# relay_control.net
KiCad netlist of a schematic drawn in EAGLE
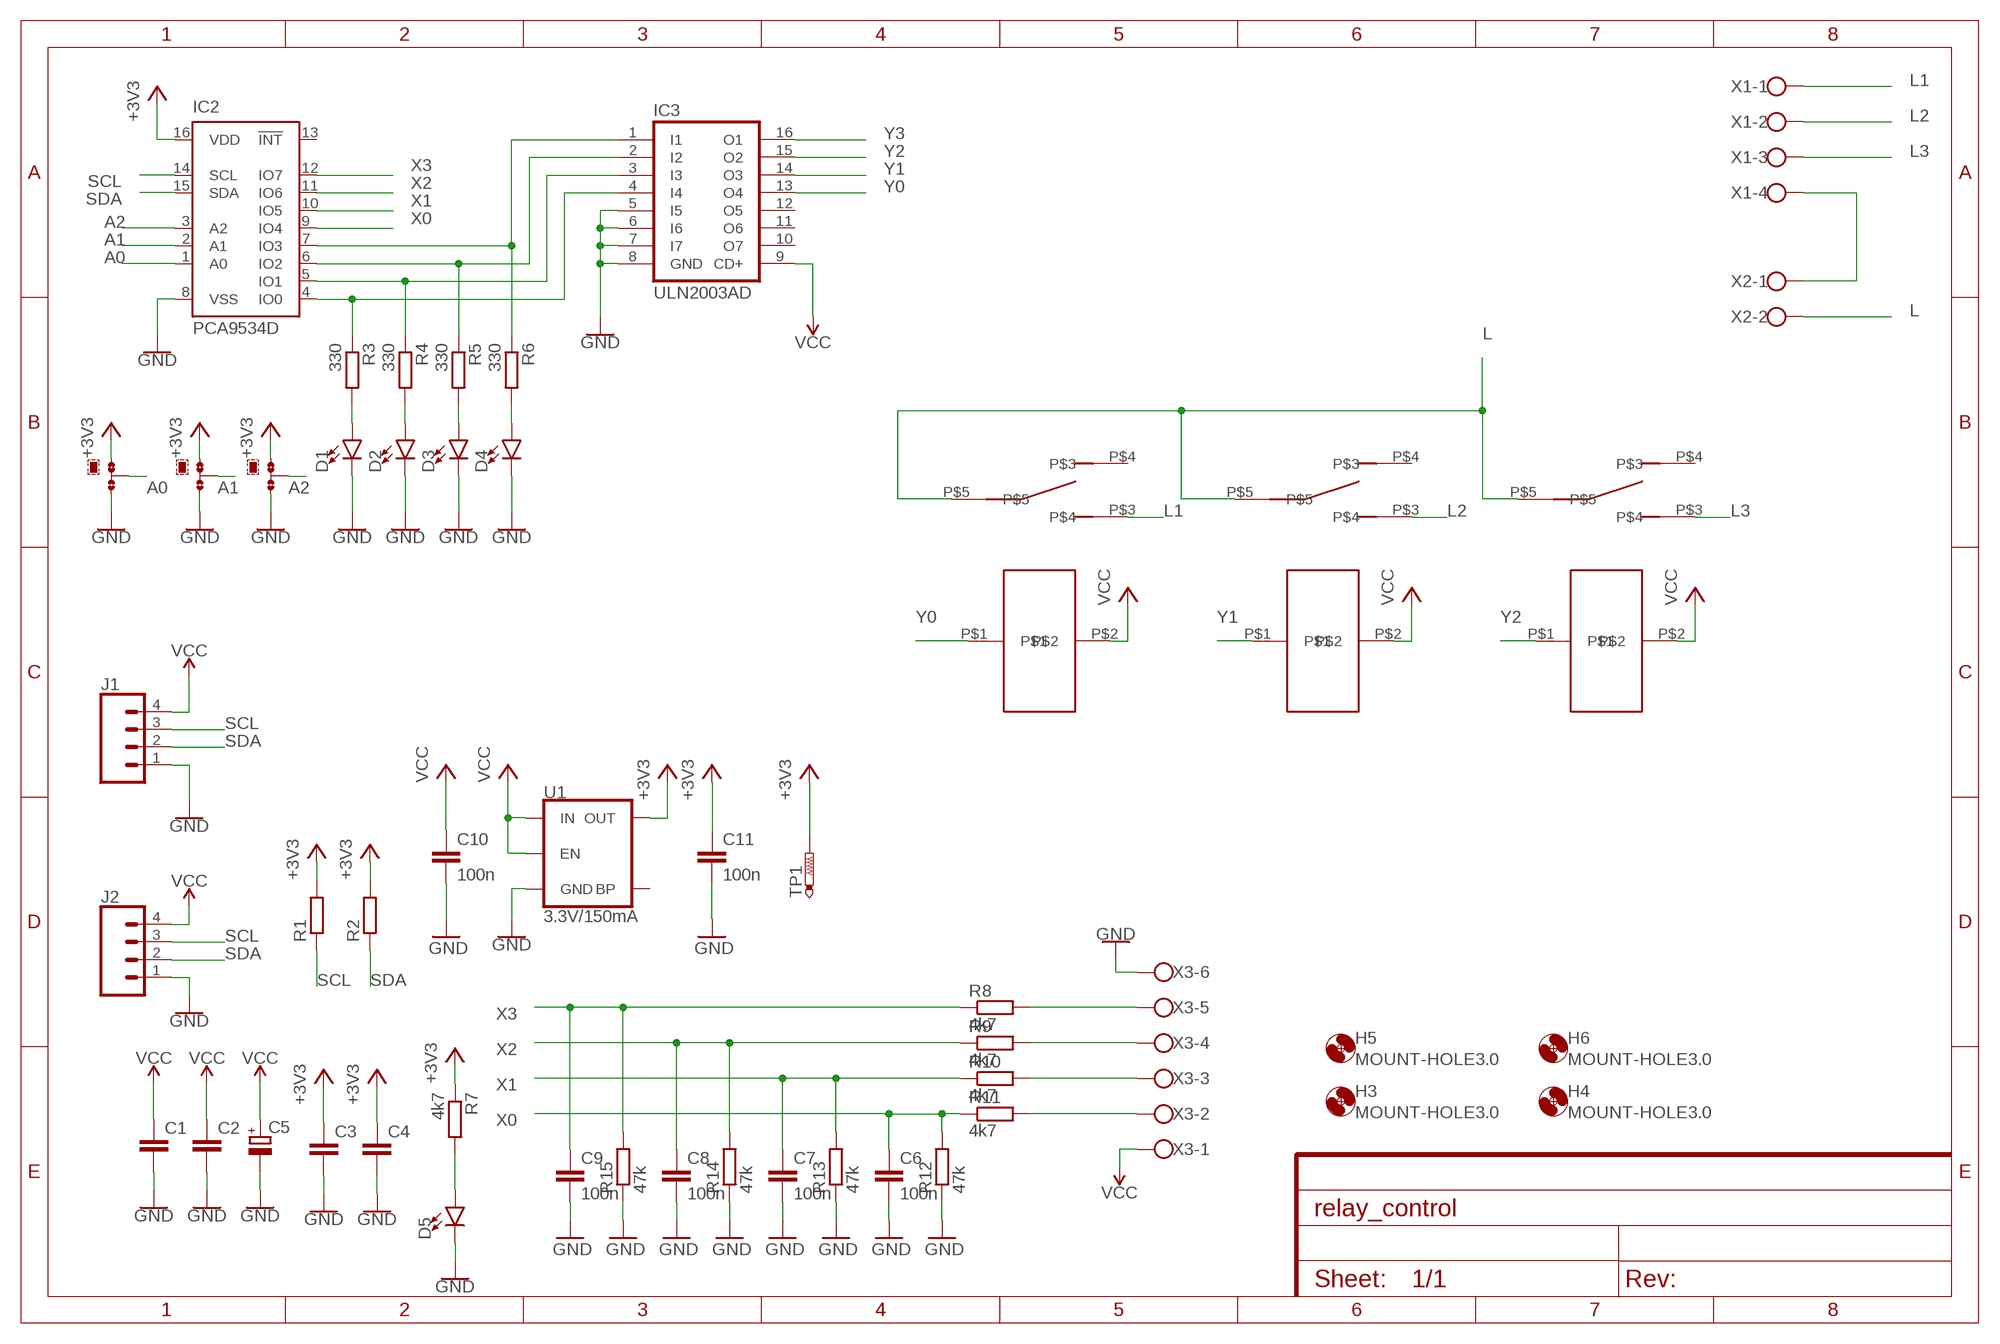
[diagram p0: schematic, sheet 1]

(export (version "E")
  (design (tool "Eeschema 10.0.6"))
  (components
    (comp (ref "C1")
      (value "C-EUC0805")
      (footprint "eagle-import:C0805")
      (libsource (lib "eagle-import") (part "C-EUC0805"))
    )
    (comp (ref "C2")
      (value "C-EUC0805")
      (footprint "eagle-import:C0805")
      (libsource (lib "eagle-import") (part "C-EUC0805"))
    )
    (comp (ref "C3")
      (value "C-EUC0805")
      (footprint "eagle-import:C0805")
      (libsource (lib "eagle-import") (part "C-EUC0805"))
    )
    (comp (ref "C4")
      (value "C-EUC0805")
      (footprint "eagle-import:C0805")
      (libsource (lib "eagle-import") (part "C-EUC0805"))
    )
    (comp (ref "C5")
      (value "CPOL-EU150CLZ-1014")
      (footprint "eagle-import:150CLZ-1014")
      (libsource (lib "eagle-import") (part "CPOL-EU150CLZ-1014"))
    )
    (comp (ref "C6")
      (value "100n")
      (footprint "eagle-import:C0805")
      (libsource (lib "eagle-import") (part "C-EUC0805"))
    )
    (comp (ref "C7")
      (value "100n")
      (footprint "eagle-import:C0805")
      (libsource (lib "eagle-import") (part "C-EUC0805"))
    )
    (comp (ref "C8")
      (value "100n")
      (footprint "eagle-import:C0805")
      (libsource (lib "eagle-import") (part "C-EUC0805"))
    )
    (comp (ref "C9")
      (value "100n")
      (footprint "eagle-import:C0805")
      (libsource (lib "eagle-import") (part "C-EUC0805"))
    )
    (comp (ref "C10")
      (value "100n")
      (footprint "eagle-import:C0805")
      (libsource (lib "eagle-import") (part "C-EUC0805"))
    )
    (comp (ref "C11")
      (value "100n")
      (footprint "eagle-import:C0805")
      (libsource (lib "eagle-import") (part "C-EUC0805"))
    )
    (comp (ref "D1")
      (value "LED1206")
      (footprint "eagle-import:LED-1206")
      (libsource (lib "eagle-import") (part "LED1206"))
    )
    (comp (ref "D2")
      (value "LED1206")
      (footprint "eagle-import:LED-1206")
      (libsource (lib "eagle-import") (part "LED1206"))
    )
    (comp (ref "D3")
      (value "LED1206")
      (footprint "eagle-import:LED-1206")
      (libsource (lib "eagle-import") (part "LED1206"))
    )
    (comp (ref "D4")
      (value "LED1206")
      (footprint "eagle-import:LED-1206")
      (libsource (lib "eagle-import") (part "LED1206"))
    )
    (comp (ref "D5")
      (value "LED1206")
      (footprint "eagle-import:LED-1206")
      (libsource (lib "eagle-import") (part "LED1206"))
    )
    (comp (ref "H3")
      (value "MOUNT-HOLE3.0")
      (footprint "eagle-import:3,0")
      (libsource (lib "eagle-import") (part "MOUNT-HOLE3.0"))
    )
    (comp (ref "H4")
      (value "MOUNT-HOLE3.0")
      (footprint "eagle-import:3,0")
      (libsource (lib "eagle-import") (part "MOUNT-HOLE3.0"))
    )
    (comp (ref "H5")
      (value "MOUNT-HOLE3.0")
      (footprint "eagle-import:3,0")
      (libsource (lib "eagle-import") (part "MOUNT-HOLE3.0"))
    )
    (comp (ref "H6")
      (value "MOUNT-HOLE3.0")
      (footprint "eagle-import:3,0")
      (libsource (lib "eagle-import") (part "MOUNT-HOLE3.0"))
    )
    (comp (ref "IC2")
      (value "PCA9534D")
      (footprint "eagle-import:SO16W")
      (fields (field (name "MPN") "PCA9534DB"))
      (libsource (lib "eagle-import") (part "PCA9534D"))
    )
    (comp (ref "IC3")
      (value "ULN2003AD")
      (footprint "eagle-import:SO16")
      (libsource (lib "eagle-import") (part "ULN2003AD"))
    )
    (comp (ref "J1")
      (value "CONN_04POLAR")
      (footprint "eagle-import:MOLEX-1X4")
      (libsource (lib "eagle-import") (part "CONN_04POLAR"))
    )
    (comp (ref "J2")
      (value "CONN_04POLAR")
      (footprint "eagle-import:MOLEX-1X4")
      (libsource (lib "eagle-import") (part "CONN_04POLAR"))
    )
    (comp (ref "JMP1")
      (value "0R-JUMPA")
      (footprint "eagle-import:A0R-JMP")
      (libsource (lib "eagle-import") (part "0R-JUMPA"))
    )
    (comp (ref "JMP2")
      (value "0R-JUMPA")
      (footprint "eagle-import:A0R-JMP")
      (libsource (lib "eagle-import") (part "0R-JUMPA"))
    )
    (comp (ref "JMP3")
      (value "0R-JUMPA")
      (footprint "eagle-import:A0R-JMP")
      (libsource (lib "eagle-import") (part "0R-JUMPA"))
    )
    (comp (ref "R1")
      (value "R-EU_M0805")
      (footprint "eagle-import:M0805")
      (libsource (lib "eagle-import") (part "R-EU_M0805"))
    )
    (comp (ref "R2")
      (value "R-EU_M0805")
      (footprint "eagle-import:M0805")
      (libsource (lib "eagle-import") (part "R-EU_M0805"))
    )
    (comp (ref "R3")
      (value "330")
      (footprint "eagle-import:M0805")
      (libsource (lib "eagle-import") (part "R-EU_M0805"))
    )
    (comp (ref "R4")
      (value "330")
      (footprint "eagle-import:M0805")
      (libsource (lib "eagle-import") (part "R-EU_M0805"))
    )
    (comp (ref "R5")
      (value "330")
      (footprint "eagle-import:M0805")
      (libsource (lib "eagle-import") (part "R-EU_M0805"))
    )
    (comp (ref "R6")
      (value "330")
      (footprint "eagle-import:M0805")
      (libsource (lib "eagle-import") (part "R-EU_M0805"))
    )
    (comp (ref "R7")
      (value "4k7")
      (footprint "eagle-import:M0805")
      (libsource (lib "eagle-import") (part "R-EU_M0805"))
    )
    (comp (ref "R8")
      (value "4k7")
      (footprint "eagle-import:M0805")
      (libsource (lib "eagle-import") (part "R-EU_M0805"))
    )
    (comp (ref "R9")
      (value "4k7")
      (footprint "eagle-import:M0805")
      (libsource (lib "eagle-import") (part "R-EU_M0805"))
    )
    (comp (ref "R10")
      (value "4k7")
      (footprint "eagle-import:M0805")
      (libsource (lib "eagle-import") (part "R-EU_M0805"))
    )
    (comp (ref "R11")
      (value "4k7")
      (footprint "eagle-import:M0805")
      (libsource (lib "eagle-import") (part "R-EU_M0805"))
    )
    (comp (ref "R12")
      (value "47k")
      (footprint "eagle-import:M0805")
      (libsource (lib "eagle-import") (part "R-EU_M0805"))
    )
    (comp (ref "R13")
      (value "47k")
      (footprint "eagle-import:M0805")
      (libsource (lib "eagle-import") (part "R-EU_M0805"))
    )
    (comp (ref "R14")
      (value "47k")
      (footprint "eagle-import:M0805")
      (libsource (lib "eagle-import") (part "R-EU_M0805"))
    )
    (comp (ref "R15")
      (value "47k")
      (footprint "eagle-import:M0805")
      (libsource (lib "eagle-import") (part "R-EU_M0805"))
    )
    (comp (ref "TP1")
      (value "PTR1B2,54")
      (footprint "eagle-import:B2,54")
      (libsource (lib "eagle-import") (part "PTR1B2,54"))
    )
    (comp (ref "U$1")
      (value "T9G_RELAY")
      (footprint "eagle-import:T9G_RELAY")
      (libsource (lib "eagle-import") (part "T9G_RELAY"))
    )
    (comp (ref "U$2")
      (value "T9G_RELAY")
      (footprint "eagle-import:T9G_RELAY")
      (libsource (lib "eagle-import") (part "T9G_RELAY"))
    )
    (comp (ref "U$3")
      (value "T9G_RELAY")
      (footprint "eagle-import:T9G_RELAY")
      (libsource (lib "eagle-import") (part "T9G_RELAY"))
    )
    (comp (ref "U1")
      (value "3.3V/150mA")
      (footprint "eagle-import:SOT23-5")
      (libsource (lib "eagle-import") (part "V_REG_MIC52053.3V"))
    )
    (comp (ref "X1")
      (value "W239-104")
      (footprint "eagle-import:W239-104")
      (libsource (lib "eagle-import") (part "W239-104"))
    )
    (comp (ref "X2")
      (value "W239-302")
      (footprint "eagle-import:W239-302")
      (libsource (lib "eagle-import") (part "W239-302"))
    )
    (comp (ref "X3")
      (value "W237-6")
      (footprint "eagle-import:W237-6")
      (libsource (lib "eagle-import") (part "W237-6"))
    )
  )
  (nets
    (net (code "1") (name "+3V3") (class "Default")
      (node (ref "C11") (pin "1") (pinfunction "1_1") (pintype "passive"))
      (node (ref "C3") (pin "1") (pinfunction "1_1") (pintype "passive"))
      (node (ref "C4") (pin "1") (pinfunction "1_1") (pintype "passive"))
      (node (ref "IC2") (pin "16") (pinfunction "VDD_16") (pintype "power_in"))
      (node (ref "JMP1") (pin "1") (pinfunction "1_1") (pintype "passive"))
      (node (ref "JMP2") (pin "1") (pinfunction "1_1") (pintype "passive"))
      (node (ref "JMP3") (pin "1") (pinfunction "1_1") (pintype "passive"))
      (node (ref "R1") (pin "2") (pinfunction "2_2") (pintype "passive"))
      (node (ref "R2") (pin "2") (pinfunction "2_2") (pintype "passive"))
      (node (ref "R7") (pin "1") (pinfunction "1_1") (pintype "passive"))
      (node (ref "TP1") (pin "TP") (pinfunction "TP_TP") (pintype "input"))
      (node (ref "U1") (pin "5") (pinfunction "OUT_5") (pintype "passive"))
    )
    (net (code "2") (name "/A0") (class "Default")
      (node (ref "IC2") (pin "1") (pinfunction "A0_1") (pintype "input"))
      (node (ref "JMP1") (pin "2") (pinfunction "2_2") (pintype "passive"))
    )
    (net (code "3") (name "/A1") (class "Default")
      (node (ref "IC2") (pin "2") (pinfunction "A1_2") (pintype "input"))
      (node (ref "JMP2") (pin "2") (pinfunction "2_2") (pintype "passive"))
    )
    (net (code "4") (name "/A2") (class "Default")
      (node (ref "IC2") (pin "3") (pinfunction "A2_3") (pintype "input"))
      (node (ref "JMP3") (pin "2") (pinfunction "2_2") (pintype "passive"))
    )
    (net (code "5") (name "/L") (class "Default")
      (node (ref "U$1") (pin "P$5") (pinfunction "P$5_P$5") (pintype "bidirectional"))
      (node (ref "U$2") (pin "P$5") (pinfunction "P$5_P$5") (pintype "bidirectional"))
      (node (ref "U$3") (pin "P$5") (pinfunction "P$5_P$5") (pintype "bidirectional"))
      (node (ref "X2") (pin "2") (pinfunction "KL_2") (pintype "passive"))
    )
    (net (code "6") (name "/L1") (class "Default")
      (node (ref "U$1") (pin "P$3") (pinfunction "P$4_P$3") (pintype "bidirectional"))
      (node (ref "X1") (pin "1") (pinfunction "KL_1") (pintype "passive"))
    )
    (net (code "7") (name "/L2") (class "Default")
      (node (ref "U$2") (pin "P$3") (pinfunction "P$4_P$3") (pintype "bidirectional"))
      (node (ref "X1") (pin "2") (pinfunction "KL_2") (pintype "passive"))
    )
    (net (code "8") (name "/L3") (class "Default")
      (node (ref "U$3") (pin "P$3") (pinfunction "P$4_P$3") (pintype "bidirectional"))
      (node (ref "X1") (pin "3") (pinfunction "KL_3") (pintype "passive"))
    )
    (net (code "9") (name "/SCL") (class "Default")
      (node (ref "IC2") (pin "14") (pinfunction "SCL_14") (pintype "input"))
      (node (ref "J1") (pin "3") (pinfunction "3_3") (pintype "passive"))
      (node (ref "J2") (pin "3") (pinfunction "3_3") (pintype "passive"))
      (node (ref "R1") (pin "1") (pinfunction "1_1") (pintype "passive"))
    )
    (net (code "10") (name "/SDA") (class "Default")
      (node (ref "IC2") (pin "15") (pinfunction "SDA_15") (pintype "bidirectional"))
      (node (ref "J1") (pin "2") (pinfunction "2_2") (pintype "passive"))
      (node (ref "J2") (pin "2") (pinfunction "2_2") (pintype "passive"))
      (node (ref "R2") (pin "1") (pinfunction "1_1") (pintype "passive"))
    )
    (net (code "11") (name "/X0") (class "Default")
      (node (ref "C6") (pin "1") (pinfunction "1_1") (pintype "passive"))
      (node (ref "IC2") (pin "9") (pinfunction "IO4_9") (pintype "bidirectional"))
      (node (ref "R11") (pin "1") (pinfunction "1_1") (pintype "passive"))
      (node (ref "R12") (pin "2") (pinfunction "2_2") (pintype "passive"))
    )
    (net (code "12") (name "/X1") (class "Default")
      (node (ref "C7") (pin "1") (pinfunction "1_1") (pintype "passive"))
      (node (ref "IC2") (pin "10") (pinfunction "IO5_10") (pintype "bidirectional"))
      (node (ref "R10") (pin "1") (pinfunction "1_1") (pintype "passive"))
      (node (ref "R13") (pin "2") (pinfunction "2_2") (pintype "passive"))
    )
    (net (code "13") (name "/X2") (class "Default")
      (node (ref "C8") (pin "1") (pinfunction "1_1") (pintype "passive"))
      (node (ref "IC2") (pin "11") (pinfunction "IO6_11") (pintype "bidirectional"))
      (node (ref "R14") (pin "2") (pinfunction "2_2") (pintype "passive"))
      (node (ref "R9") (pin "1") (pinfunction "1_1") (pintype "passive"))
    )
    (net (code "14") (name "/X3") (class "Default")
      (node (ref "C9") (pin "1") (pinfunction "1_1") (pintype "passive"))
      (node (ref "IC2") (pin "12") (pinfunction "IO7_12") (pintype "bidirectional"))
      (node (ref "R15") (pin "2") (pinfunction "2_2") (pintype "passive"))
      (node (ref "R8") (pin "1") (pinfunction "1_1") (pintype "passive"))
    )
    (net (code "15") (name "/Y0") (class "Default")
      (node (ref "IC3") (pin "13") (pinfunction "O4_13") (pintype "open_collector"))
      (node (ref "U$1") (pin "P$1") (pinfunction "P$1_P$1") (pintype "bidirectional"))
    )
    (net (code "16") (name "/Y1") (class "Default")
      (node (ref "IC3") (pin "14") (pinfunction "O3_14") (pintype "open_collector"))
      (node (ref "U$2") (pin "P$1") (pinfunction "P$1_P$1") (pintype "bidirectional"))
    )
    (net (code "17") (name "/Y2") (class "Default")
      (node (ref "IC3") (pin "15") (pinfunction "O2_15") (pintype "open_collector"))
      (node (ref "U$3") (pin "P$1") (pinfunction "P$1_P$1") (pintype "bidirectional"))
    )
    (net (code "18") (name "/Y3") (class "Default")
      (node (ref "IC3") (pin "16") (pinfunction "O1_16") (pintype "open_collector"))
    )
    (net (code "19") (name "GND") (class "Default")
      (node (ref "C1") (pin "2") (pinfunction "2_2") (pintype "passive"))
      (node (ref "C10") (pin "2") (pinfunction "2_2") (pintype "passive"))
      (node (ref "C11") (pin "2") (pinfunction "2_2") (pintype "passive"))
      (node (ref "C2") (pin "2") (pinfunction "2_2") (pintype "passive"))
      (node (ref "C3") (pin "2") (pinfunction "2_2") (pintype "passive"))
      (node (ref "C4") (pin "2") (pinfunction "2_2") (pintype "passive"))
      (node (ref "C5") (pin "-") (pinfunction "-_-") (pintype "passive"))
      (node (ref "C6") (pin "2") (pinfunction "2_2") (pintype "passive"))
      (node (ref "C7") (pin "2") (pinfunction "2_2") (pintype "passive"))
      (node (ref "C8") (pin "2") (pinfunction "2_2") (pintype "passive"))
      (node (ref "C9") (pin "2") (pinfunction "2_2") (pintype "passive"))
      (node (ref "D1") (pin "C") (pinfunction "C_C") (pintype "passive"))
      (node (ref "D2") (pin "C") (pinfunction "C_C") (pintype "passive"))
      (node (ref "D3") (pin "C") (pinfunction "C_C") (pintype "passive"))
      (node (ref "D4") (pin "C") (pinfunction "C_C") (pintype "passive"))
      (node (ref "D5") (pin "C") (pinfunction "C_C") (pintype "passive"))
      (node (ref "IC2") (pin "8") (pinfunction "VSS_8") (pintype "power_in"))
      (node (ref "IC3") (pin "5") (pinfunction "I5_5") (pintype "input"))
      (node (ref "IC3") (pin "6") (pinfunction "I6_6") (pintype "input"))
      (node (ref "IC3") (pin "7") (pinfunction "I7_7") (pintype "input"))
      (node (ref "IC3") (pin "8") (pinfunction "GND_8") (pintype "power_in"))
      (node (ref "J1") (pin "1") (pinfunction "1_1") (pintype "passive"))
      (node (ref "J2") (pin "1") (pinfunction "1_1") (pintype "passive"))
      (node (ref "JMP1") (pin "3") (pinfunction "3_3") (pintype "passive"))
      (node (ref "JMP2") (pin "3") (pinfunction "3_3") (pintype "passive"))
      (node (ref "JMP3") (pin "3") (pinfunction "3_3") (pintype "passive"))
      (node (ref "R12") (pin "1") (pinfunction "1_1") (pintype "passive"))
      (node (ref "R13") (pin "1") (pinfunction "1_1") (pintype "passive"))
      (node (ref "R14") (pin "1") (pinfunction "1_1") (pintype "passive"))
      (node (ref "R15") (pin "1") (pinfunction "1_1") (pintype "passive"))
      (node (ref "U1") (pin "2") (pinfunction "GND_2") (pintype "input"))
      (node (ref "X3") (pin "6") (pinfunction "KL_6") (pintype "passive"))
    )
    (net (code "20") (name "Net-(D1-PadA)") (class "Default")
      (node (ref "D1") (pin "A") (pinfunction "A_A") (pintype "passive"))
      (node (ref "R3") (pin "2") (pinfunction "2_2") (pintype "passive"))
    )
    (net (code "21") (name "Net-(D2-PadA)") (class "Default")
      (node (ref "D2") (pin "A") (pinfunction "A_A") (pintype "passive"))
      (node (ref "R4") (pin "2") (pinfunction "2_2") (pintype "passive"))
    )
    (net (code "22") (name "Net-(D3-PadA)") (class "Default")
      (node (ref "D3") (pin "A") (pinfunction "A_A") (pintype "passive"))
      (node (ref "R5") (pin "2") (pinfunction "2_2") (pintype "passive"))
    )
    (net (code "23") (name "Net-(D4-PadA)") (class "Default")
      (node (ref "D4") (pin "A") (pinfunction "A_A") (pintype "passive"))
      (node (ref "R6") (pin "2") (pinfunction "2_2") (pintype "passive"))
    )
    (net (code "24") (name "Net-(D5-PadA)") (class "Default")
      (node (ref "D5") (pin "A") (pinfunction "A_A") (pintype "passive"))
      (node (ref "R7") (pin "2") (pinfunction "2_2") (pintype "passive"))
    )
    (net (code "25") (name "Net-(IC2-IO0)") (class "Default")
      (node (ref "IC2") (pin "4") (pinfunction "IO0_4") (pintype "bidirectional"))
      (node (ref "IC3") (pin "4") (pinfunction "I4_4") (pintype "input"))
      (node (ref "R3") (pin "1") (pinfunction "1_1") (pintype "passive"))
    )
    (net (code "26") (name "Net-(IC2-IO1)") (class "Default")
      (node (ref "IC2") (pin "5") (pinfunction "IO1_5") (pintype "bidirectional"))
      (node (ref "IC3") (pin "3") (pinfunction "I3_3") (pintype "input"))
      (node (ref "R4") (pin "1") (pinfunction "1_1") (pintype "passive"))
    )
    (net (code "27") (name "Net-(IC2-IO2)") (class "Default")
      (node (ref "IC2") (pin "6") (pinfunction "IO2_6") (pintype "bidirectional"))
      (node (ref "IC3") (pin "2") (pinfunction "I2_2") (pintype "input"))
      (node (ref "R5") (pin "1") (pinfunction "1_1") (pintype "passive"))
    )
    (net (code "28") (name "Net-(IC2-IO3)") (class "Default")
      (node (ref "IC2") (pin "7") (pinfunction "IO3_7") (pintype "bidirectional"))
      (node (ref "IC3") (pin "1") (pinfunction "I1_1") (pintype "input"))
      (node (ref "R6") (pin "1") (pinfunction "1_1") (pintype "passive"))
    )
    (net (code "29") (name "Net-(X1D-KL)") (class "Default")
      (node (ref "X1") (pin "4") (pinfunction "KL_4") (pintype "passive"))
      (node (ref "X2") (pin "1") (pinfunction "KL_1") (pintype "passive"))
    )
    (net (code "30") (name "Net-(X3B-KL)") (class "Default")
      (node (ref "R11") (pin "2") (pinfunction "2_2") (pintype "passive"))
      (node (ref "X3") (pin "2") (pinfunction "KL_2") (pintype "passive"))
    )
    (net (code "31") (name "Net-(X3C-KL)") (class "Default")
      (node (ref "R10") (pin "2") (pinfunction "2_2") (pintype "passive"))
      (node (ref "X3") (pin "3") (pinfunction "KL_3") (pintype "passive"))
    )
    (net (code "32") (name "Net-(X3D-KL)") (class "Default")
      (node (ref "R9") (pin "2") (pinfunction "2_2") (pintype "passive"))
      (node (ref "X3") (pin "4") (pinfunction "KL_4") (pintype "passive"))
    )
    (net (code "33") (name "Net-(X3E-KL)") (class "Default")
      (node (ref "R8") (pin "2") (pinfunction "2_2") (pintype "passive"))
      (node (ref "X3") (pin "5") (pinfunction "KL_5") (pintype "passive"))
    )
    (net (code "34") (name "VCC") (class "Default")
      (node (ref "C1") (pin "1") (pinfunction "1_1") (pintype "passive"))
      (node (ref "C10") (pin "1") (pinfunction "1_1") (pintype "passive"))
      (node (ref "C2") (pin "1") (pinfunction "1_1") (pintype "passive"))
      (node (ref "C5") (pin "+") (pinfunction "+_+") (pintype "passive"))
      (node (ref "IC3") (pin "9") (pinfunction "CD+_9") (pintype "passive"))
      (node (ref "J1") (pin "4") (pinfunction "4_4") (pintype "passive"))
      (node (ref "J2") (pin "4") (pinfunction "4_4") (pintype "passive"))
      (node (ref "U$1") (pin "P$2") (pinfunction "P$2_P$2") (pintype "bidirectional"))
      (node (ref "U$2") (pin "P$2") (pinfunction "P$2_P$2") (pintype "bidirectional"))
      (node (ref "U$3") (pin "P$2") (pinfunction "P$2_P$2") (pintype "bidirectional"))
      (node (ref "U1") (pin "1") (pinfunction "IN_1") (pintype "input"))
      (node (ref "U1") (pin "3") (pinfunction "EN_3") (pintype "input"))
      (node (ref "X3") (pin "1") (pinfunction "KL_1") (pintype "passive"))
    )
    (net (code "35") (name "unconnected-(IC2-~{INT}-Pad13)") (class "Default")
      (node (ref "IC2") (pin "13") (pinfunction "~{INT}_13") (pintype "open_collector"))
    )
    (net (code "36") (name "unconnected-(IC3-O5-Pad12)") (class "Default")
      (node (ref "IC3") (pin "12") (pinfunction "O5_12") (pintype "open_collector"))
    )
    (net (code "37") (name "unconnected-(IC3-O6-Pad11)") (class "Default")
      (node (ref "IC3") (pin "11") (pinfunction "O6_11") (pintype "open_collector"))
    )
    (net (code "38") (name "unconnected-(IC3-O7-Pad10)") (class "Default")
      (node (ref "IC3") (pin "10") (pinfunction "O7_10") (pintype "open_collector"))
    )
    (net (code "39") (name "unconnected-(U$1-P$3-PadP$4)") (class "Default")
      (node (ref "U$1") (pin "P$4") (pinfunction "P$3_P$4") (pintype "bidirectional"))
    )
    (net (code "40") (name "unconnected-(U$2-P$3-PadP$4)") (class "Default")
      (node (ref "U$2") (pin "P$4") (pinfunction "P$3_P$4") (pintype "bidirectional"))
    )
    (net (code "41") (name "unconnected-(U$3-P$3-PadP$4)") (class "Default")
      (node (ref "U$3") (pin "P$4") (pinfunction "P$3_P$4") (pintype "bidirectional"))
    )
    (net (code "42") (name "unconnected-(U1-BP-Pad4)") (class "Default")
      (node (ref "U1") (pin "4") (pinfunction "BP_4") (pintype "input"))
    )
  )
)
